# USB3_0_UART.net
KiCad netlist of a schematic drawn in Altium Designer
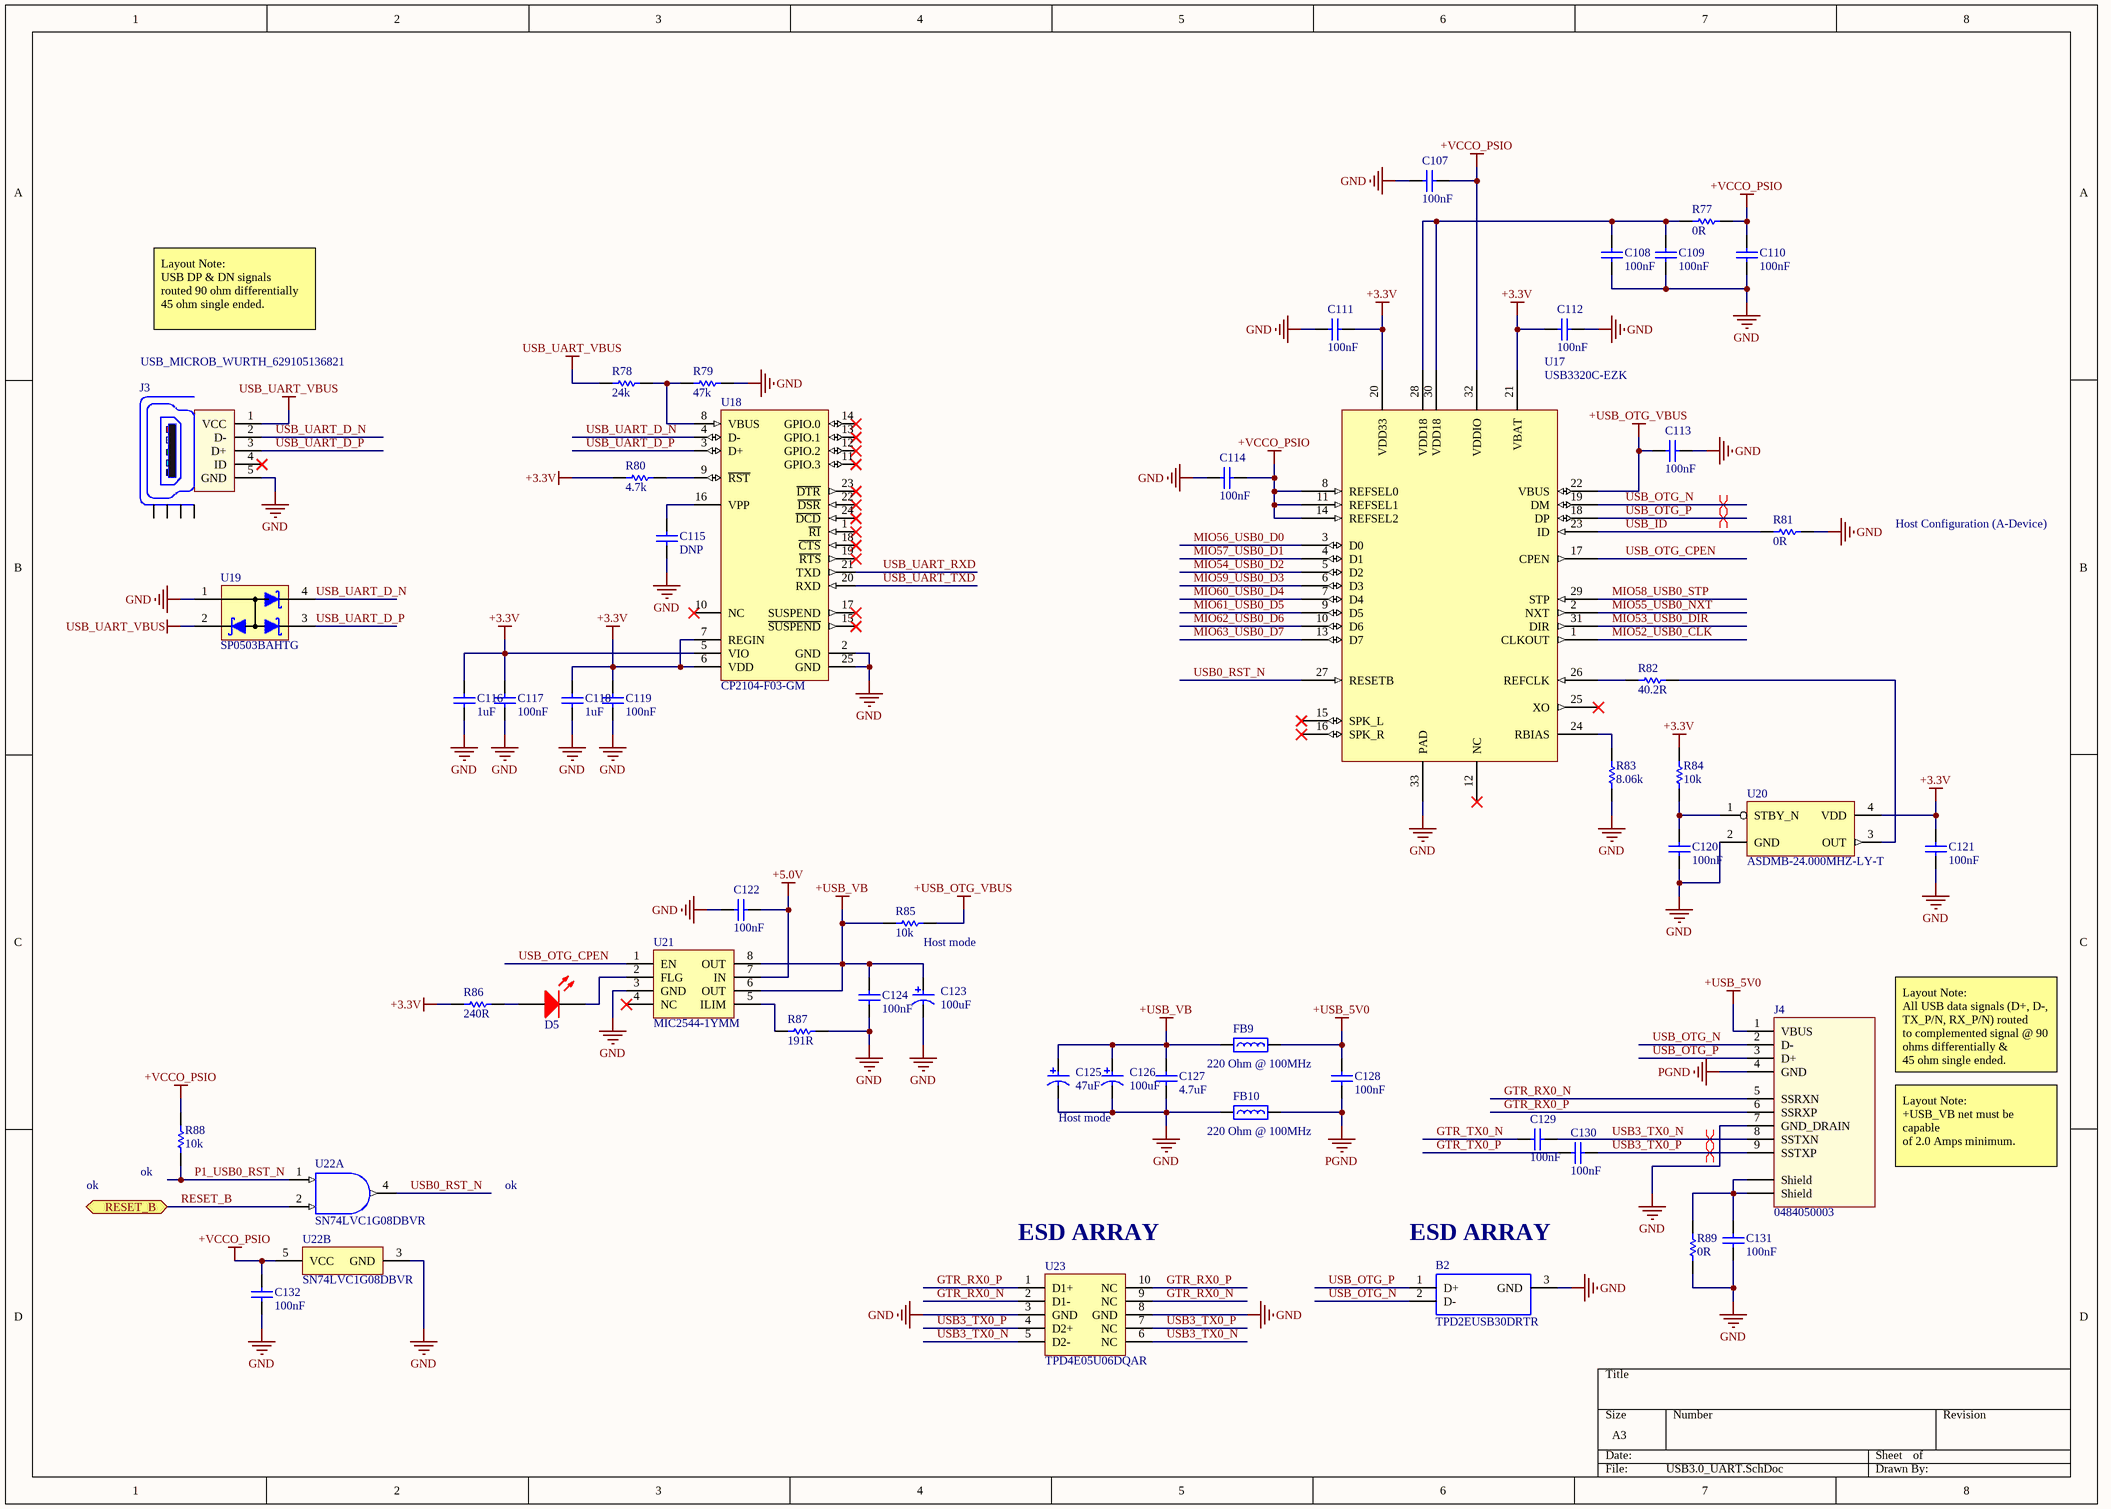
[diagram p0: USB3.0_UART.SchDoc]

(export (version "E")
  (design (tool "Eeschema 10.0.6"))
  (components
    (comp (ref "B2")
      (value "TPD2EUSB30DRTR")
      (footprint "SOTFL35P100X50-3N")
      (description "Texas Instruments TPD2EUSB30DRTR Dual Bi-Directional TVS Diode Array, 45W peak, 3-Pin SOT")
      (fields (field (name "DIGI-KEY PART NUMBER") "296-25509-1-ND"))
      (libsource (lib "Ultrascale_SchLib") (part "D TPD2EUSB30DRTR"))
    )
    (comp (ref "C107")
      (value "100nF")
      (footprint "CAPC1005L_0402")
      (description "CAP CER 0.1UF 25V X7R 0402")
      (fields (field (name "VOLTAGE") "25V") (field (name "TOLERANCE") "10%"))
      (libsource (lib "Ultrascale_SchLib") (part "CAPCER0402X7R100N25V_10T"))
    )
    (comp (ref "C108")
      (value "100nF")
      (footprint "CAPC1005L_0402")
      (description "CAP CER 0.1UF 25V X7R 0402")
      (fields (field (name "VOLTAGE") "25V") (field (name "TOLERANCE") "10%"))
      (libsource (lib "Ultrascale_SchLib") (part "CAPCER0402X7R100N25V_10T"))
    )
    (comp (ref "C109")
      (value "100nF")
      (footprint "CAPC1005L_0402")
      (description "CAP CER 0.1UF 25V X7R 0402")
      (fields (field (name "VOLTAGE") "25V") (field (name "TOLERANCE") "10%"))
      (libsource (lib "Ultrascale_SchLib") (part "CAPCER0402X7R100N25V_10T"))
    )
    (comp (ref "C110")
      (value "100nF")
      (footprint "CAPC1005L_0402")
      (description "CAP CER 0.1UF 25V X7R 0402")
      (fields (field (name "VOLTAGE") "25V") (field (name "TOLERANCE") "10%"))
      (libsource (lib "Ultrascale_SchLib") (part "CAPCER0402X7R100N25V_10T"))
    )
    (comp (ref "C111")
      (value "100nF")
      (footprint "CAPC1005L_0402")
      (description "CAP CER 0.1UF 25V X7R 0402")
      (fields (field (name "VOLTAGE") "25V") (field (name "TOLERANCE") "10%"))
      (libsource (lib "Ultrascale_SchLib") (part "CAPCER0402X7R100N25V_10T"))
    )
    (comp (ref "C112")
      (value "100nF")
      (footprint "CAPC1005L_0402")
      (description "CAP CER 0.1UF 25V X7R 0402")
      (fields (field (name "VOLTAGE") "25V") (field (name "TOLERANCE") "10%"))
      (libsource (lib "Ultrascale_SchLib") (part "CAPCER0402X7R100N25V_10T"))
    )
    (comp (ref "C113")
      (value "100nF")
      (footprint "CAPC1005L_0402")
      (description "CAP CER 0.1UF 25V X7R 0402")
      (fields (field (name "VOLTAGE") "25V") (field (name "TOLERANCE") "10%"))
      (libsource (lib "Ultrascale_SchLib") (part "CAPCER0402X7R100N25V_10T"))
    )
    (comp (ref "C114")
      (value "100nF")
      (footprint "CAPC1005L_0402")
      (description "CAP CER 0.1UF 25V X7R 0402")
      (fields (field (name "VOLTAGE") "25V") (field (name "TOLERANCE") "10%"))
      (libsource (lib "Ultrascale_SchLib") (part "CAPCER0402X7R100N25V_10T"))
    )
    (comp (ref "C115")
      (value "DNP")
      (footprint "CAPC1005L_0402")
      (description "0402 Package Cap Footprint")
      (libsource (lib "Ultrascale_SchLib") (part "CAPCER0402"))
    )
    (comp (ref "C116")
      (value "1uF")
      (footprint "CAPC1005L_0402")
      (description "CAP CER 1UF 16V X5R 0402")
      (fields (field (name "VOLTAGE") "16V") (field (name "TOLERANCE") "20%"))
      (libsource (lib "Ultrascale_SchLib") (part "CAPCER0402X5R1U16V_20T"))
    )
    (comp (ref "C117")
      (value "100nF")
      (footprint "CAPC1005L_0402")
      (description "CAP CER 0.1UF 25V X7R 0402")
      (fields (field (name "VOLTAGE") "25V") (field (name "TOLERANCE") "10%"))
      (libsource (lib "Ultrascale_SchLib") (part "CAPCER0402X7R100N25V_10T"))
    )
    (comp (ref "C118")
      (value "1uF")
      (footprint "CAPC1005L_0402")
      (description "CAP CER 1UF 16V X5R 0402")
      (fields (field (name "VOLTAGE") "16V") (field (name "TOLERANCE") "20%"))
      (libsource (lib "Ultrascale_SchLib") (part "CAPCER0402X5R1U16V_20T"))
    )
    (comp (ref "C119")
      (value "100nF")
      (footprint "CAPC1005L_0402")
      (description "CAP CER 0.1UF 25V X7R 0402")
      (fields (field (name "VOLTAGE") "25V") (field (name "TOLERANCE") "10%"))
      (libsource (lib "Ultrascale_SchLib") (part "CAPCER0402X7R100N25V_10T"))
    )
    (comp (ref "C120")
      (value "100nF")
      (footprint "CAPC1005L_0402")
      (description "CAP CER 0.1UF 25V X7R 0402")
      (fields (field (name "VOLTAGE") "25V") (field (name "TOLERANCE") "10%"))
      (libsource (lib "Ultrascale_SchLib") (part "CAPCER0402X7R100N25V_10T"))
    )
    (comp (ref "C121")
      (value "100nF")
      (footprint "CAPC1005L_0402")
      (description "CAP CER 0.1UF 25V X7R 0402")
      (fields (field (name "VOLTAGE") "25V") (field (name "TOLERANCE") "10%"))
      (libsource (lib "Ultrascale_SchLib") (part "CAPCER0402X7R100N25V_10T"))
    )
    (comp (ref "C122")
      (value "100nF")
      (footprint "CAPC1005L_0402")
      (description "CAP CER 0.1UF 25V X7R 0402")
      (fields (field (name "VOLTAGE") "25V") (field (name "TOLERANCE") "10%"))
      (libsource (lib "Ultrascale_SchLib") (part "CAPCER0402X7R100N25V_10T"))
    )
    (comp (ref "C123")
      (value "100uF")
      (footprint "AVX_TAN_F95_P_0905")
      (description "CAP TANT 100UF 6.3V 20% 0805")
      (fields (field (name "VOLTAGE") "6.3V") (field (name "TOLERANCE") "20%"))
      (libsource (lib "Ultrascale_SchLib") (part "CAPELE0905TAN100U6V3_20T"))
    )
    (comp (ref "C124")
      (value "100nF")
      (footprint "CAPC1005L_0402")
      (description "CAP CER 0.1UF 25V X7R 0402")
      (fields (field (name "VOLTAGE") "25V") (field (name "TOLERANCE") "10%"))
      (libsource (lib "Ultrascale_SchLib") (part "CAPCER0402X7R100N25V_10T"))
    )
    (comp (ref "C125")
      (value "47uF")
      (footprint "AVX_TAN_F38_M_0603")
      (description "CAP TANT POLY 47UF 6.3V SMD")
      (fields (field (name "VOLTAGE") "6.3V") (field (name "TOLERANCE") "20%"))
      (libsource (lib "Ultrascale_SchLib") (part "CAPELE0603TAN47U6V3_20T"))
    )
    (comp (ref "C126")
      (value "100uF")
      (footprint "AVX_TAN_F95_P_0905")
      (description "CAP TANT 100UF 6.3V 20% 0805")
      (fields (field (name "VOLTAGE") "6.3V") (field (name "TOLERANCE") "20%"))
      (libsource (lib "Ultrascale_SchLib") (part "CAPELE0905TAN100U6V3_20T"))
    )
    (comp (ref "C127")
      (value "4.7uF")
      (footprint "CAPC1005L_0402")
      (description "CAP CER 4.7UF 10V X5R 0402")
      (fields (field (name "VOLTAGE") "10V") (field (name "TOLERANCE") "10%"))
      (libsource (lib "Ultrascale_SchLib") (part "CAPCER0402X5R4U710V_10T"))
    )
    (comp (ref "C128")
      (value "100nF")
      (footprint "CAPC1005L_0402")
      (description "CAP CER 0.1UF 25V X7R 0402")
      (fields (field (name "VOLTAGE") "25V") (field (name "TOLERANCE") "10%"))
      (libsource (lib "Ultrascale_SchLib") (part "CAPCER0402X7R100N25V_10T"))
    )
    (comp (ref "C129")
      (value "100nF")
      (footprint "CAPC1005L_0402")
      (description "CAP CER 0.1UF 25V X7R 0402")
      (fields (field (name "VOLTAGE") "25V") (field (name "TOLERANCE") "10%"))
      (libsource (lib "Ultrascale_SchLib") (part "CAPCER0402X7R100N25V_10T"))
    )
    (comp (ref "C130")
      (value "100nF")
      (footprint "CAPC1005L_0402")
      (description "CAP CER 0.1UF 25V X7R 0402")
      (fields (field (name "VOLTAGE") "25V") (field (name "TOLERANCE") "10%"))
      (libsource (lib "Ultrascale_SchLib") (part "CAPCER0402X7R100N25V_10T"))
    )
    (comp (ref "C131")
      (value "100nF")
      (footprint "CAPC1005L_0402")
      (description "CAP CER 0.1UF 25V X7R 0402")
      (fields (field (name "VOLTAGE") "25V") (field (name "TOLERANCE") "10%"))
      (libsource (lib "Ultrascale_SchLib") (part "CAPCER0402X7R100N25V_10T"))
    )
    (comp (ref "C132")
      (value "100nF")
      (footprint "CAPC1005L_0402")
      (description "CAP CER 0.1UF 25V X7R 0402")
      (fields (field (name "VOLTAGE") "25V") (field (name "TOLERANCE") "10%"))
      (libsource (lib "Ultrascale_SchLib") (part "CAPCER0402X7R100N25V_10T"))
    )
    (comp (ref "D5")
      (value "LED0603RED")
      (footprint "LED0603RED")
      (description "LED RED DIFFUSED 0603 SMD")
      (libsource (lib "Ultrascale_SchLib") (part "LED0603RED"))
    )
    (comp (ref "FB9")
      (value "BEAD0603_220_2A5_40M")
      (footprint "INDC1608N_0603")
      (description "FERRITE BEAD 220 OHM 0603 1LN")
      (fields (field (name "IMPEDANCE @ FREQUENCY") "220 Ohm @ 100MHz"))
      (libsource (lib "Ultrascale_SchLib") (part "BEAD0603_220_2A5_40M"))
    )
    (comp (ref "FB10")
      (value "BEAD0603_220_2A5_40M")
      (footprint "INDC1608N_0603")
      (description "FERRITE BEAD 220 OHM 0603 1LN")
      (fields (field (name "IMPEDANCE @ FREQUENCY") "220 Ohm @ 100MHz"))
      (libsource (lib "Ultrascale_SchLib") (part "BEAD0603_220_2A5_40M"))
    )
    (comp (ref "J3")
      (value "USB_MICROB_WURTH_629105136821")
      (footprint "USB_MICROB_WURTH_629105136821")
      (description "CONN RCPT USB MICRO B R/A SMT")
      (libsource (lib "Ultrascale_SchLib") (part "USB_MICROB_WURTH_629105136821"))
    )
    (comp (ref "J4")
      (value "0484050003")
      (footprint "USB30_RA_0484050003")
      (description "USB 3.0 RA REC TH TYPE A")
      (libsource (lib "Ultrascale_SchLib") (part "0484050003"))
    )
    (comp (ref "R77")
      (value "0R")
      (footprint "RESC1005L_0402")
      (description "RES SMD 0 OHM JUMPER 1/10W 0402")
      (fields (field (name "POWER") "1/10W") (field (name "Comment") "RES0402_0R_0W1"))
      (libsource (lib "Ultrascale_SchLib") (part "RES0402_0R_0W1"))
    )
    (comp (ref "R78")
      (value "24k")
      (footprint "RESC1005L_0402")
      (description "RES SMD 24K OHM 1% 1/10W 0402")
      (fields (field (name "POWER") "1/10W") (field (name "TOLERANCE") "1%"))
      (libsource (lib "Ultrascale_SchLib") (part "RES0402_24K_0W1"))
    )
    (comp (ref "R79")
      (value "47k")
      (footprint "RESC1005L_0402")
      (description "RES SMD 47K OHM 1% 1/10W 0402")
      (fields (field (name "POWER") "1/10W") (field (name "TOLERANCE") "1%"))
      (libsource (lib "Ultrascale_SchLib") (part "RES0402_47K_0W1"))
    )
    (comp (ref "R80")
      (value "4.7k")
      (footprint "RESC1005L_0402")
      (description "RES SMD 4.7K OHM 1% 1/10W 0402")
      (fields (field (name "POWER") "1/10W") (field (name "TOLERANCE") "1%"))
      (libsource (lib "Ultrascale_SchLib") (part "RES0402_4K7_0W1_1T"))
    )
    (comp (ref "R81")
      (value "0R")
      (footprint "RESC1005L_0402")
      (description "RES SMD 0 OHM JUMPER 1/10W 0402")
      (fields (field (name "POWER") "1/10W") (field (name "Comment") "RES0402_0R_0W1"))
      (libsource (lib "Ultrascale_SchLib") (part "RES0402_0R_0W1"))
    )
    (comp (ref "R82")
      (value "40.2R")
      (footprint "RESC1005L_0402")
      (description "RES SMD 40.2 OHM 1% 1/10W 0402")
      (fields (field (name "POWER") "1/10W") (field (name "TOLERANCE") "1%"))
      (libsource (lib "Ultrascale_SchLib") (part "RES0402_40R2_0W1_1T"))
    )
    (comp (ref "R83")
      (value "8.06k")
      (footprint "RESC1005L_0402")
      (description "RES SMD 8.06K OHM 1% 1/10W 0402")
      (fields (field (name "POWER") "1/10W") (field (name "TOLERANCE") "1%"))
      (libsource (lib "Ultrascale_SchLib") (part "RES0402_8K06_0W1_1T"))
    )
    (comp (ref "R84")
      (value "10k")
      (footprint "RESC1005L_0402")
      (description "RES SMD 10K OHM 0.5% 1/16W 0402")
      (fields (field (name "POWER") "1/16W") (field (name "TOLERANCE") "0.5%"))
      (libsource (lib "Ultrascale_SchLib") (part "RES0402_10K_0W1_05T"))
    )
    (comp (ref "R85")
      (value "10k")
      (footprint "RESC1005L_0402")
      (description "RES SMD 10K OHM 0.5% 1/16W 0402")
      (fields (field (name "POWER") "1/16W") (field (name "TOLERANCE") "0.5%"))
      (libsource (lib "Ultrascale_SchLib") (part "RES0402_10K_0W1_05T"))
    )
    (comp (ref "R86")
      (value "240R")
      (footprint "RESC1005L_0402")
      (description "RES SMD 240 OHM 1% 1/10W 0402")
      (fields (field (name "POWER") "1/10W") (field (name "TOLERANCE") "1%"))
      (libsource (lib "Ultrascale_SchLib") (part "RES0402_240R_0W1_1T"))
    )
    (comp (ref "R87")
      (value "191R")
      (footprint "RESC1005L_0402")
      (description "RES SMD 191 OHM 1% 1/10W 0402")
      (fields (field (name "POWER") "1/10W") (field (name "TOLERANCE") "1%"))
      (libsource (lib "Ultrascale_SchLib") (part "RES0402_191R_0W1_1T"))
    )
    (comp (ref "R88")
      (value "10k")
      (footprint "RESC1005L_0402")
      (description "RES SMD 10K OHM 0.5% 1/16W 0402")
      (fields (field (name "POWER") "1/16W") (field (name "TOLERANCE") "0.5%"))
      (libsource (lib "Ultrascale_SchLib") (part "RES0402_10K_0W1_05T"))
    )
    (comp (ref "R89")
      (value "0R")
      (footprint "RESC1005L_0402")
      (description "RES SMD 0 OHM JUMPER 1/10W 0402")
      (fields (field (name "POWER") "1/10W") (field (name "Comment") "RES0402_0R_0W1"))
      (libsource (lib "Ultrascale_SchLib") (part "RES0402_0R_0W1"))
    )
    (comp (ref "U17")
      (value "USB3320C-EZK")
      (footprint "QFN50P500X500X100_HS-33N")
      (description "IC TXRX USB 2.0 FLEXPWR 32QFN")
      (libsource (lib "Ultrascale_SchLib") (part "USB3320C-EZK"))
    )
    (comp (ref "U18")
      (value "CP2104-F03-GM")
      (footprint "SLAB-QFN-24-2675x2675TP_L")
      (libsource (lib "Ultrascale_SchLib") (part "CP2104-F03-GM"))
    )
    (comp (ref "U19")
      (value "SP0503BAHTG")
      (footprint "SP0503BAHT_SOT143")
      (description "IC TXRX USB 2.0 FLEXPWR 32QFN")
      (libsource (lib "Ultrascale_SchLib") (part "SP0503BAHTG"))
    )
    (comp (ref "U20")
      (value "ASDMB-24.000MHZ-LY-T")
      (footprint "ASDMB")
      (description "OSC MEMS 24.000MHZ CMOS SMD")
      (libsource (lib "Ultrascale_SchLib") (part "ASDMB-24.000MHZ-LY-T"))
    )
    (comp (ref "U21")
      (value "MIC2544-1YMM")
      (footprint "TPD4E05U06DQAR")
      (description "IC SW CURR LIMIT HI SIDE 8-MSOP")
      (libsource (lib "Ultrascale_SchLib") (part "MIC2544-1YMM"))
    )
    (comp (ref "U22")
      (value "SN74LVC1G08DBVR")
      (footprint "DBV0005A_N")
      (description "Single 2-Input Positive-AND Gate, DBV0005A, LARGE T&R")
      (fields (field (name "GENERIC PART NUMBER") "SN74LVC1G08"))
      (libsource (lib "Ultrascale_SchLib") (part "SN74LVC1G08DBVR"))
    )
    (comp (ref "U23")
      (value "TPD4E05U06DQAR")
      (footprint "TPD4E05U06DQAR")
      (description "TVS DIODE 5.5VWM 14VC 10SON")
      (libsource (lib "Ultrascale_SchLib") (part "TPD4E05U06DQAR"))
    )
  )
  (nets
    (net (code "1") (name "+3.3V") (class "Default")
      (node (ref "C111") (pin "2") (pinfunction "2_2") (pintype "passive"))
      (node (ref "C112") (pin "2") (pinfunction "2_2") (pintype "passive"))
      (node (ref "C116") (pin "1") (pinfunction "1_1") (pintype "passive"))
      (node (ref "C117") (pin "1") (pinfunction "1_1") (pintype "passive"))
      (node (ref "C118") (pin "1") (pinfunction "1_1") (pintype "passive"))
      (node (ref "C119") (pin "1") (pinfunction "1_1") (pintype "passive"))
      (node (ref "C121") (pin "1") (pinfunction "1_1") (pintype "passive"))
      (node (ref "R80") (pin "1") (pinfunction "1_1") (pintype "passive"))
      (node (ref "R84") (pin "1") (pinfunction "1_1") (pintype "passive"))
      (node (ref "R86") (pin "1") (pinfunction "1_1") (pintype "passive"))
      (node (ref "U17") (pin "20") (pinfunction "VDD33_20") (pintype "passive"))
      (node (ref "U17") (pin "21") (pinfunction "VBAT_21") (pintype "passive"))
      (node (ref "U18") (pin "5") (pinfunction "VIO_5") (pintype "power_in"))
      (node (ref "U18") (pin "6") (pinfunction "VDD_6") (pintype "power_in"))
      (node (ref "U18") (pin "7") (pinfunction "REGIN_7") (pintype "power_in"))
      (node (ref "U20") (pin "4") (pinfunction "VDD_4") (pintype "passive"))
    )
    (net (code "2") (name "+5.0V") (class "Default")
      (node (ref "C122") (pin "2") (pinfunction "2_2") (pintype "passive"))
      (node (ref "U21") (pin "7") (pinfunction "IN_7") (pintype "passive"))
    )
    (net (code "3") (name "+USB_5V0") (class "Default")
      (node (ref "C128") (pin "1") (pinfunction "1_1") (pintype "passive"))
      (node (ref "FB9") (pin "2") (pinfunction "2_2") (pintype "passive"))
      (node (ref "J4") (pin "1") (pinfunction "VBUS_1") (pintype "passive"))
    )
    (net (code "4") (name "+USB_OTG_VBUS") (class "Default")
      (node (ref "C113") (pin "1") (pinfunction "1_1") (pintype "passive"))
      (node (ref "R85") (pin "2") (pinfunction "2_2") (pintype "passive"))
      (node (ref "U17") (pin "22") (pinfunction "VBUS_22") (pintype "bidirectional"))
    )
    (net (code "5") (name "+USB_VB") (class "Default")
      (node (ref "C123") (pin "1") (pinfunction "1_1") (pintype "passive"))
      (node (ref "C124") (pin "1") (pinfunction "1_1") (pintype "passive"))
      (node (ref "C125") (pin "1") (pinfunction "1_1") (pintype "passive"))
      (node (ref "C126") (pin "1") (pinfunction "1_1") (pintype "passive"))
      (node (ref "C127") (pin "2") (pinfunction "2_2") (pintype "passive"))
      (node (ref "FB9") (pin "1") (pinfunction "1_1") (pintype "passive"))
      (node (ref "R85") (pin "1") (pinfunction "1_1") (pintype "passive"))
      (node (ref "U21") (pin "6") (pinfunction "OUT_6") (pintype "passive"))
      (node (ref "U21") (pin "8") (pinfunction "OUT_8") (pintype "passive"))
    )
    (net (code "6") (name "+VCCO_PSIO") (class "Default")
      (node (ref "C107") (pin "2") (pinfunction "2_2") (pintype "passive"))
      (node (ref "C110") (pin "2") (pinfunction "2_2") (pintype "passive"))
      (node (ref "C114") (pin "2") (pinfunction "2_2") (pintype "passive"))
      (node (ref "C132") (pin "1") (pinfunction "1_1") (pintype "passive"))
      (node (ref "R77") (pin "2") (pinfunction "2_2") (pintype "passive"))
      (node (ref "R88") (pin "2") (pinfunction "2_2") (pintype "passive"))
      (node (ref "U17") (pin "11") (pinfunction "REFSEL1_11") (pintype "input"))
      (node (ref "U17") (pin "14") (pinfunction "REFSEL2_14") (pintype "input"))
      (node (ref "U17") (pin "32") (pinfunction "VDDIO_32") (pintype "passive"))
      (node (ref "U17") (pin "8") (pinfunction "REFSEL0_8") (pintype "input"))
      (node (ref "U22") (pin "5") (pinfunction "VCC_5") (pintype "power_in"))
    )
    (net (code "7") (name "/GTR_RX0_N") (class "Default")
      (node (ref "J4") (pin "5") (pinfunction "SSRXN_5") (pintype "passive"))
      (node (ref "U23") (pin "2") (pinfunction "D1-_2") (pintype "passive"))
      (node (ref "U23") (pin "9") (pinfunction "NC_9") (pintype "passive"))
    )
    (net (code "8") (name "/GTR_RX0_P") (class "Default")
      (node (ref "J4") (pin "6") (pinfunction "SSRXP_6") (pintype "passive"))
      (node (ref "U23") (pin "1") (pinfunction "D1+_1") (pintype "passive"))
      (node (ref "U23") (pin "10") (pinfunction "NC_10") (pintype "passive"))
    )
    (net (code "9") (name "/GTR_TX0_N") (class "Default")
      (node (ref "C129") (pin "1") (pinfunction "1_1") (pintype "passive"))
    )
    (net (code "10") (name "/GTR_TX0_P") (class "Default")
      (node (ref "C130") (pin "1") (pinfunction "1_1") (pintype "passive"))
    )
    (net (code "11") (name "/MIO52_USB0_CLK") (class "Default")
      (node (ref "U17") (pin "1") (pinfunction "CLKOUT_1") (pintype "output"))
    )
    (net (code "12") (name "/MIO53_USB0_DIR") (class "Default")
      (node (ref "U17") (pin "31") (pinfunction "DIR_31") (pintype "output"))
    )
    (net (code "13") (name "/MIO54_USB0_D2") (class "Default")
      (node (ref "U17") (pin "5") (pinfunction "D2_5") (pintype "bidirectional"))
    )
    (net (code "14") (name "/MIO55_USB0_NXT") (class "Default")
      (node (ref "U17") (pin "2") (pinfunction "NXT_2") (pintype "output"))
    )
    (net (code "15") (name "/MIO56_USB0_D0") (class "Default")
      (node (ref "U17") (pin "3") (pinfunction "D0_3") (pintype "bidirectional"))
    )
    (net (code "16") (name "/MIO57_USB0_D1") (class "Default")
      (node (ref "U17") (pin "4") (pinfunction "D1_4") (pintype "bidirectional"))
    )
    (net (code "17") (name "/MIO58_USB0_STP") (class "Default")
      (node (ref "U17") (pin "29") (pinfunction "STP_29") (pintype "input"))
    )
    (net (code "18") (name "/MIO59_USB0_D3") (class "Default")
      (node (ref "U17") (pin "6") (pinfunction "D3_6") (pintype "bidirectional"))
    )
    (net (code "19") (name "/MIO60_USB0_D4") (class "Default")
      (node (ref "U17") (pin "7") (pinfunction "D4_7") (pintype "bidirectional"))
    )
    (net (code "20") (name "/MIO61_USB0_D5") (class "Default")
      (node (ref "U17") (pin "9") (pinfunction "D5_9") (pintype "bidirectional"))
    )
    (net (code "21") (name "/MIO62_USB0_D6") (class "Default")
      (node (ref "U17") (pin "10") (pinfunction "D6_10") (pintype "bidirectional"))
    )
    (net (code "22") (name "/MIO63_USB0_D7") (class "Default")
      (node (ref "U17") (pin "13") (pinfunction "D7_13") (pintype "bidirectional"))
    )
    (net (code "23") (name "/P1_USB0_RST_N") (class "Default")
      (node (ref "R88") (pin "1") (pinfunction "1_1") (pintype "passive"))
      (node (ref "U22") (pin "1") (pinfunction "A_1") (pintype "input"))
    )
    (net (code "24") (name "/RESET_B") (class "Default")
      (node (ref "U22") (pin "2") (pinfunction "B_2") (pintype "input"))
    )
    (net (code "25") (name "/USB0_RST_N") (class "Default")
      (node (ref "U17") (pin "27") (pinfunction "RESETB_27") (pintype "input"))
      (node (ref "U22") (pin "4") (pinfunction "Y_4") (pintype "output"))
    )
    (net (code "26") (name "/USB3_TX0_N") (class "Default")
      (node (ref "C129") (pin "2") (pinfunction "2_2") (pintype "passive"))
      (node (ref "J4") (pin "8") (pinfunction "SSTXN_8") (pintype "passive"))
      (node (ref "U23") (pin "5") (pinfunction "D2-_5") (pintype "passive"))
      (node (ref "U23") (pin "6") (pinfunction "NC_6") (pintype "passive"))
    )
    (net (code "27") (name "/USB3_TX0_P") (class "Default")
      (node (ref "C130") (pin "2") (pinfunction "2_2") (pintype "passive"))
      (node (ref "J4") (pin "9") (pinfunction "SSTXP_9") (pintype "passive"))
      (node (ref "U23") (pin "4") (pinfunction "D2+_4") (pintype "passive"))
      (node (ref "U23") (pin "7") (pinfunction "NC_7") (pintype "passive"))
    )
    (net (code "28") (name "/USB_ID") (class "Default")
      (node (ref "R81") (pin "1") (pinfunction "1_1") (pintype "passive"))
      (node (ref "U17") (pin "23") (pinfunction "ID_23") (pintype "input"))
    )
    (net (code "29") (name "/USB_OTG_CPEN") (class "Default")
      (node (ref "U17") (pin "17") (pinfunction "CPEN_17") (pintype "output"))
      (node (ref "U21") (pin "1") (pinfunction "EN_1") (pintype "passive"))
    )
    (net (code "30") (name "/USB_OTG_N") (class "Default")
      (node (ref "B2") (pin "2") (pinfunction "D-_2") (pintype "passive"))
      (node (ref "J4") (pin "2") (pinfunction "D-_2") (pintype "passive"))
      (node (ref "U17") (pin "19") (pinfunction "DM_19") (pintype "bidirectional"))
    )
    (net (code "31") (name "/USB_OTG_P") (class "Default")
      (node (ref "B2") (pin "1") (pinfunction "D+_1") (pintype "passive"))
      (node (ref "J4") (pin "3") (pinfunction "D+_3") (pintype "passive"))
      (node (ref "U17") (pin "18") (pinfunction "DP_18") (pintype "bidirectional"))
    )
    (net (code "32") (name "/USB_UART_D_N") (class "Default")
      (node (ref "J3") (pin "2") (pinfunction "D-_2") (pintype "passive"))
      (node (ref "U18") (pin "4") (pinfunction "D-_4") (pintype "bidirectional"))
      (node (ref "U19") (pin "4") (pinfunction "4_4") (pintype "passive"))
    )
    (net (code "33") (name "/USB_UART_D_P") (class "Default")
      (node (ref "J3") (pin "3") (pinfunction "D+_3") (pintype "passive"))
      (node (ref "U18") (pin "3") (pinfunction "D+_3") (pintype "bidirectional"))
      (node (ref "U19") (pin "3") (pinfunction "3_3") (pintype "passive"))
    )
    (net (code "34") (name "/USB_UART_RXD") (class "Default")
      (node (ref "U18") (pin "21") (pinfunction "TXD_21") (pintype "output"))
    )
    (net (code "35") (name "/USB_UART_TXD") (class "Default")
      (node (ref "U18") (pin "20") (pinfunction "RXD_20") (pintype "input"))
    )
    (net (code "36") (name "GND") (class "Default")
      (node (ref "B2") (pin "3") (pinfunction "GND_3") (pintype "passive"))
      (node (ref "C107") (pin "1") (pinfunction "1_1") (pintype "passive"))
      (node (ref "C108") (pin "2") (pinfunction "2_2") (pintype "passive"))
      (node (ref "C109") (pin "1") (pinfunction "1_1") (pintype "passive"))
      (node (ref "C110") (pin "1") (pinfunction "1_1") (pintype "passive"))
      (node (ref "C111") (pin "1") (pinfunction "1_1") (pintype "passive"))
      (node (ref "C112") (pin "1") (pinfunction "1_1") (pintype "passive"))
      (node (ref "C113") (pin "2") (pinfunction "2_2") (pintype "passive"))
      (node (ref "C114") (pin "1") (pinfunction "1_1") (pintype "passive"))
      (node (ref "C115") (pin "2") (pinfunction "2_2") (pintype "passive"))
      (node (ref "C116") (pin "2") (pinfunction "2_2") (pintype "passive"))
      (node (ref "C117") (pin "2") (pinfunction "2_2") (pintype "passive"))
      (node (ref "C118") (pin "2") (pinfunction "2_2") (pintype "passive"))
      (node (ref "C119") (pin "2") (pinfunction "2_2") (pintype "passive"))
      (node (ref "C120") (pin "2") (pinfunction "2_2") (pintype "passive"))
      (node (ref "C121") (pin "2") (pinfunction "2_2") (pintype "passive"))
      (node (ref "C122") (pin "1") (pinfunction "1_1") (pintype "passive"))
      (node (ref "C123") (pin "2") (pinfunction "2_2") (pintype "passive"))
      (node (ref "C124") (pin "2") (pinfunction "2_2") (pintype "passive"))
      (node (ref "C125") (pin "2") (pinfunction "2_2") (pintype "passive"))
      (node (ref "C126") (pin "2") (pinfunction "2_2") (pintype "passive"))
      (node (ref "C127") (pin "1") (pinfunction "1_1") (pintype "passive"))
      (node (ref "C131") (pin "2") (pinfunction "2_2") (pintype "passive"))
      (node (ref "C132") (pin "2") (pinfunction "2_2") (pintype "passive"))
      (node (ref "FB10") (pin "1") (pinfunction "1_1") (pintype "passive"))
      (node (ref "J3") (pin "5") (pinfunction "GND_5") (pintype "passive"))
      (node (ref "J4") (pin "7") (pinfunction "GND_DRAIN_7") (pintype "passive"))
      (node (ref "R79") (pin "2") (pinfunction "2_2") (pintype "passive"))
      (node (ref "R81") (pin "2") (pinfunction "2_2") (pintype "passive"))
      (node (ref "R83") (pin "2") (pinfunction "2_2") (pintype "passive"))
      (node (ref "R87") (pin "1") (pinfunction "1_1") (pintype "passive"))
      (node (ref "R89") (pin "1") (pinfunction "1_1") (pintype "passive"))
      (node (ref "U17") (pin "33") (pinfunction "PAD_33") (pintype "passive"))
      (node (ref "U18") (pin "2") (pinfunction "GND_2") (pintype "power_in"))
      (node (ref "U18") (pin "25") (pinfunction "GND_25") (pintype "power_in"))
      (node (ref "U19") (pin "1") (pinfunction "1_1") (pintype "passive"))
      (node (ref "U20") (pin "2") (pinfunction "GND_2") (pintype "passive"))
      (node (ref "U21") (pin "3") (pinfunction "GND_3") (pintype "passive"))
      (node (ref "U22") (pin "3") (pinfunction "GND_3") (pintype "power_in"))
      (node (ref "U23") (pin "3") (pinfunction "GND_3") (pintype "passive"))
      (node (ref "U23") (pin "8") (pinfunction "GND_8") (pintype "passive"))
    )
    (net (code "37") (name "Net-(C108-Pad1)") (class "Default")
      (node (ref "C108") (pin "1") (pinfunction "1_1") (pintype "passive"))
      (node (ref "C109") (pin "2") (pinfunction "2_2") (pintype "passive"))
      (node (ref "R77") (pin "1") (pinfunction "1_1") (pintype "passive"))
      (node (ref "U17") (pin "28") (pinfunction "VDD18_28") (pintype "passive"))
      (node (ref "U17") (pin "30") (pinfunction "VDD18_30") (pintype "passive"))
    )
    (net (code "38") (name "Net-(C131-Pad1)") (class "Default")
      (node (ref "C131") (pin "1") (pinfunction "1_1") (pintype "passive"))
      (node (ref "J4") (pin "MH1") (pinfunction "Shield_MH1") (pintype "passive"))
      (node (ref "J4") (pin "MH2") (pinfunction "Shield_MH2") (pintype "passive"))
      (node (ref "R89") (pin "2") (pinfunction "2_2") (pintype "passive"))
    )
    (net (code "39") (name "Net-(D5-A)") (class "Default")
      (node (ref "D5") (pin "1") (pinfunction "A_1") (pintype "passive"))
      (node (ref "R86") (pin "2") (pinfunction "2_2") (pintype "passive"))
    )
    (net (code "40") (name "Net-(D5-K)") (class "Default")
      (node (ref "D5") (pin "2") (pinfunction "K_2") (pintype "passive"))
      (node (ref "U21") (pin "2") (pinfunction "FLG_2") (pintype "passive"))
    )
    (net (code "41") (name "Net-(U17-RBIAS)") (class "Default")
      (node (ref "R83") (pin "1") (pinfunction "1_1") (pintype "passive"))
      (node (ref "U17") (pin "24") (pinfunction "RBIAS_24") (pintype "passive"))
    )
    (net (code "42") (name "Net-(U17-REFCLK)") (class "Default")
      (node (ref "R82") (pin "1") (pinfunction "1_1") (pintype "passive"))
      (node (ref "U17") (pin "26") (pinfunction "REFCLK_26") (pintype "input"))
    )
    (net (code "43") (name "Net-(U18-VBUS)") (class "Default")
      (node (ref "R78") (pin "2") (pinfunction "2_2") (pintype "passive"))
      (node (ref "R79") (pin "1") (pinfunction "1_1") (pintype "passive"))
      (node (ref "U18") (pin "8") (pinfunction "VBUS_8") (pintype "input"))
    )
    (net (code "44") (name "Net-(U18-VPP)") (class "Default")
      (node (ref "C115") (pin "1") (pinfunction "1_1") (pintype "passive"))
      (node (ref "U18") (pin "16") (pinfunction "VPP_16") (pintype "passive"))
    )
    (net (code "45") (name "Net-(U18-~{RST})") (class "Default")
      (node (ref "R80") (pin "2") (pinfunction "2_2") (pintype "passive"))
      (node (ref "U18") (pin "9") (pinfunction "~{RST}_9") (pintype "bidirectional"))
    )
    (net (code "46") (name "Net-(U20-OUT)") (class "Default")
      (node (ref "R82") (pin "2") (pinfunction "2_2") (pintype "passive"))
      (node (ref "U20") (pin "3") (pinfunction "OUT_3") (pintype "output"))
    )
    (net (code "47") (name "Net-(U20-STBY_N)") (class "Default")
      (node (ref "C120") (pin "1") (pinfunction "1_1") (pintype "passive"))
      (node (ref "R84") (pin "2") (pinfunction "2_2") (pintype "passive"))
      (node (ref "U20") (pin "1") (pinfunction "STBY_N_1") (pintype "passive"))
    )
    (net (code "48") (name "Net-(U21-ILIM)") (class "Default")
      (node (ref "R87") (pin "2") (pinfunction "2_2") (pintype "passive"))
      (node (ref "U21") (pin "5") (pinfunction "ILIM_5") (pintype "passive"))
    )
    (net (code "49") (name "PGND") (class "Default")
      (node (ref "C128") (pin "2") (pinfunction "2_2") (pintype "passive"))
      (node (ref "FB10") (pin "2") (pinfunction "2_2") (pintype "passive"))
      (node (ref "J4") (pin "4") (pinfunction "GND_4") (pintype "passive"))
    )
    (net (code "50") (name "USB_UART_VBUS") (class "Default")
      (node (ref "J3") (pin "1") (pinfunction "VCC_1") (pintype "passive"))
      (node (ref "R78") (pin "1") (pinfunction "1_1") (pintype "passive"))
      (node (ref "U19") (pin "2") (pinfunction "2_2") (pintype "passive"))
    )
    (net (code "51") (name "unconnected-(J3-ID-Pad4)") (class "Default")
      (node (ref "J3") (pin "4") (pinfunction "ID_4") (pintype "passive+no_connect"))
    )
    (net (code "52") (name "unconnected-(J3-Shield-PadZ1)") (class "Default")
      (node (ref "J3") (pin "Z1") (pinfunction "Shield_Z1") (pintype "passive"))
    )
    (net (code "53") (name "unconnected-(J3-Shield-PadZ2)") (class "Default")
      (node (ref "J3") (pin "Z2") (pinfunction "Shield_Z2") (pintype "passive"))
    )
    (net (code "54") (name "unconnected-(J3-Shield-PadZ3)") (class "Default")
      (node (ref "J3") (pin "Z3") (pinfunction "Shield_Z3") (pintype "passive"))
    )
    (net (code "55") (name "unconnected-(J3-Shield-PadZ4)") (class "Default")
      (node (ref "J3") (pin "Z4") (pinfunction "Shield_Z4") (pintype "passive"))
    )
    (net (code "56") (name "unconnected-(U17-NC-Pad12)") (class "Default")
      (node (ref "U17") (pin "12") (pinfunction "NC_12") (pintype "passive+no_connect"))
    )
    (net (code "57") (name "unconnected-(U17-SPK_L-Pad15)") (class "Default")
      (node (ref "U17") (pin "15") (pinfunction "SPK_L_15") (pintype "bidirectional+no_connect"))
    )
    (net (code "58") (name "unconnected-(U17-SPK_R-Pad16)") (class "Default")
      (node (ref "U17") (pin "16") (pinfunction "SPK_R_16") (pintype "bidirectional+no_connect"))
    )
    (net (code "59") (name "unconnected-(U17-XO-Pad25)") (class "Default")
      (node (ref "U17") (pin "25") (pinfunction "XO_25") (pintype "output+no_connect"))
    )
    (net (code "60") (name "unconnected-(U18-GPIO.0-Pad14)") (class "Default")
      (node (ref "U18") (pin "14") (pinfunction "GPIO.0_14") (pintype "bidirectional+no_connect"))
    )
    (net (code "61") (name "unconnected-(U18-GPIO.1-Pad13)") (class "Default")
      (node (ref "U18") (pin "13") (pinfunction "GPIO.1_13") (pintype "bidirectional+no_connect"))
    )
    (net (code "62") (name "unconnected-(U18-GPIO.2-Pad12)") (class "Default")
      (node (ref "U18") (pin "12") (pinfunction "GPIO.2_12") (pintype "bidirectional+no_connect"))
    )
    (net (code "63") (name "unconnected-(U18-GPIO.3-Pad11)") (class "Default")
      (node (ref "U18") (pin "11") (pinfunction "GPIO.3_11") (pintype "bidirectional+no_connect"))
    )
    (net (code "64") (name "unconnected-(U18-NC-Pad10)") (class "Default")
      (node (ref "U18") (pin "10") (pinfunction "NC_10") (pintype "passive+no_connect"))
    )
    (net (code "65") (name "unconnected-(U18-SUSPEND-Pad17)") (class "Default")
      (node (ref "U18") (pin "17") (pinfunction "SUSPEND_17") (pintype "output+no_connect"))
    )
    (net (code "66") (name "unconnected-(U18-~{CTS}-Pad18)") (class "Default")
      (node (ref "U18") (pin "18") (pinfunction "~{CTS}_18") (pintype "input+no_connect"))
    )
    (net (code "67") (name "unconnected-(U18-~{DCD}-Pad24)") (class "Default")
      (node (ref "U18") (pin "24") (pinfunction "~{DCD}_24") (pintype "input+no_connect"))
    )
    (net (code "68") (name "unconnected-(U18-~{DSR}-Pad22)") (class "Default")
      (node (ref "U18") (pin "22") (pinfunction "~{DSR}_22") (pintype "input+no_connect"))
    )
    (net (code "69") (name "unconnected-(U18-~{DTR}-Pad23)") (class "Default")
      (node (ref "U18") (pin "23") (pinfunction "~{DTR}_23") (pintype "output+no_connect"))
    )
    (net (code "70") (name "unconnected-(U18-~{RI}-Pad1)") (class "Default")
      (node (ref "U18") (pin "1") (pinfunction "~{RI}_1") (pintype "input+no_connect"))
    )
    (net (code "71") (name "unconnected-(U18-~{RTS}-Pad19)") (class "Default")
      (node (ref "U18") (pin "19") (pinfunction "~{RTS}_19") (pintype "output+no_connect"))
    )
    (net (code "72") (name "unconnected-(U18-~{SUSPEND}-Pad15)") (class "Default")
      (node (ref "U18") (pin "15") (pinfunction "~{SUSPEND}_15") (pintype "output+no_connect"))
    )
    (net (code "73") (name "unconnected-(U21-NC-Pad4)") (class "Default")
      (node (ref "U21") (pin "4") (pinfunction "NC_4") (pintype "passive+no_connect"))
    )
  )
)
